# Arduino_Dimmer.net
KiCad netlist of a schematic drawn in EasyEDA
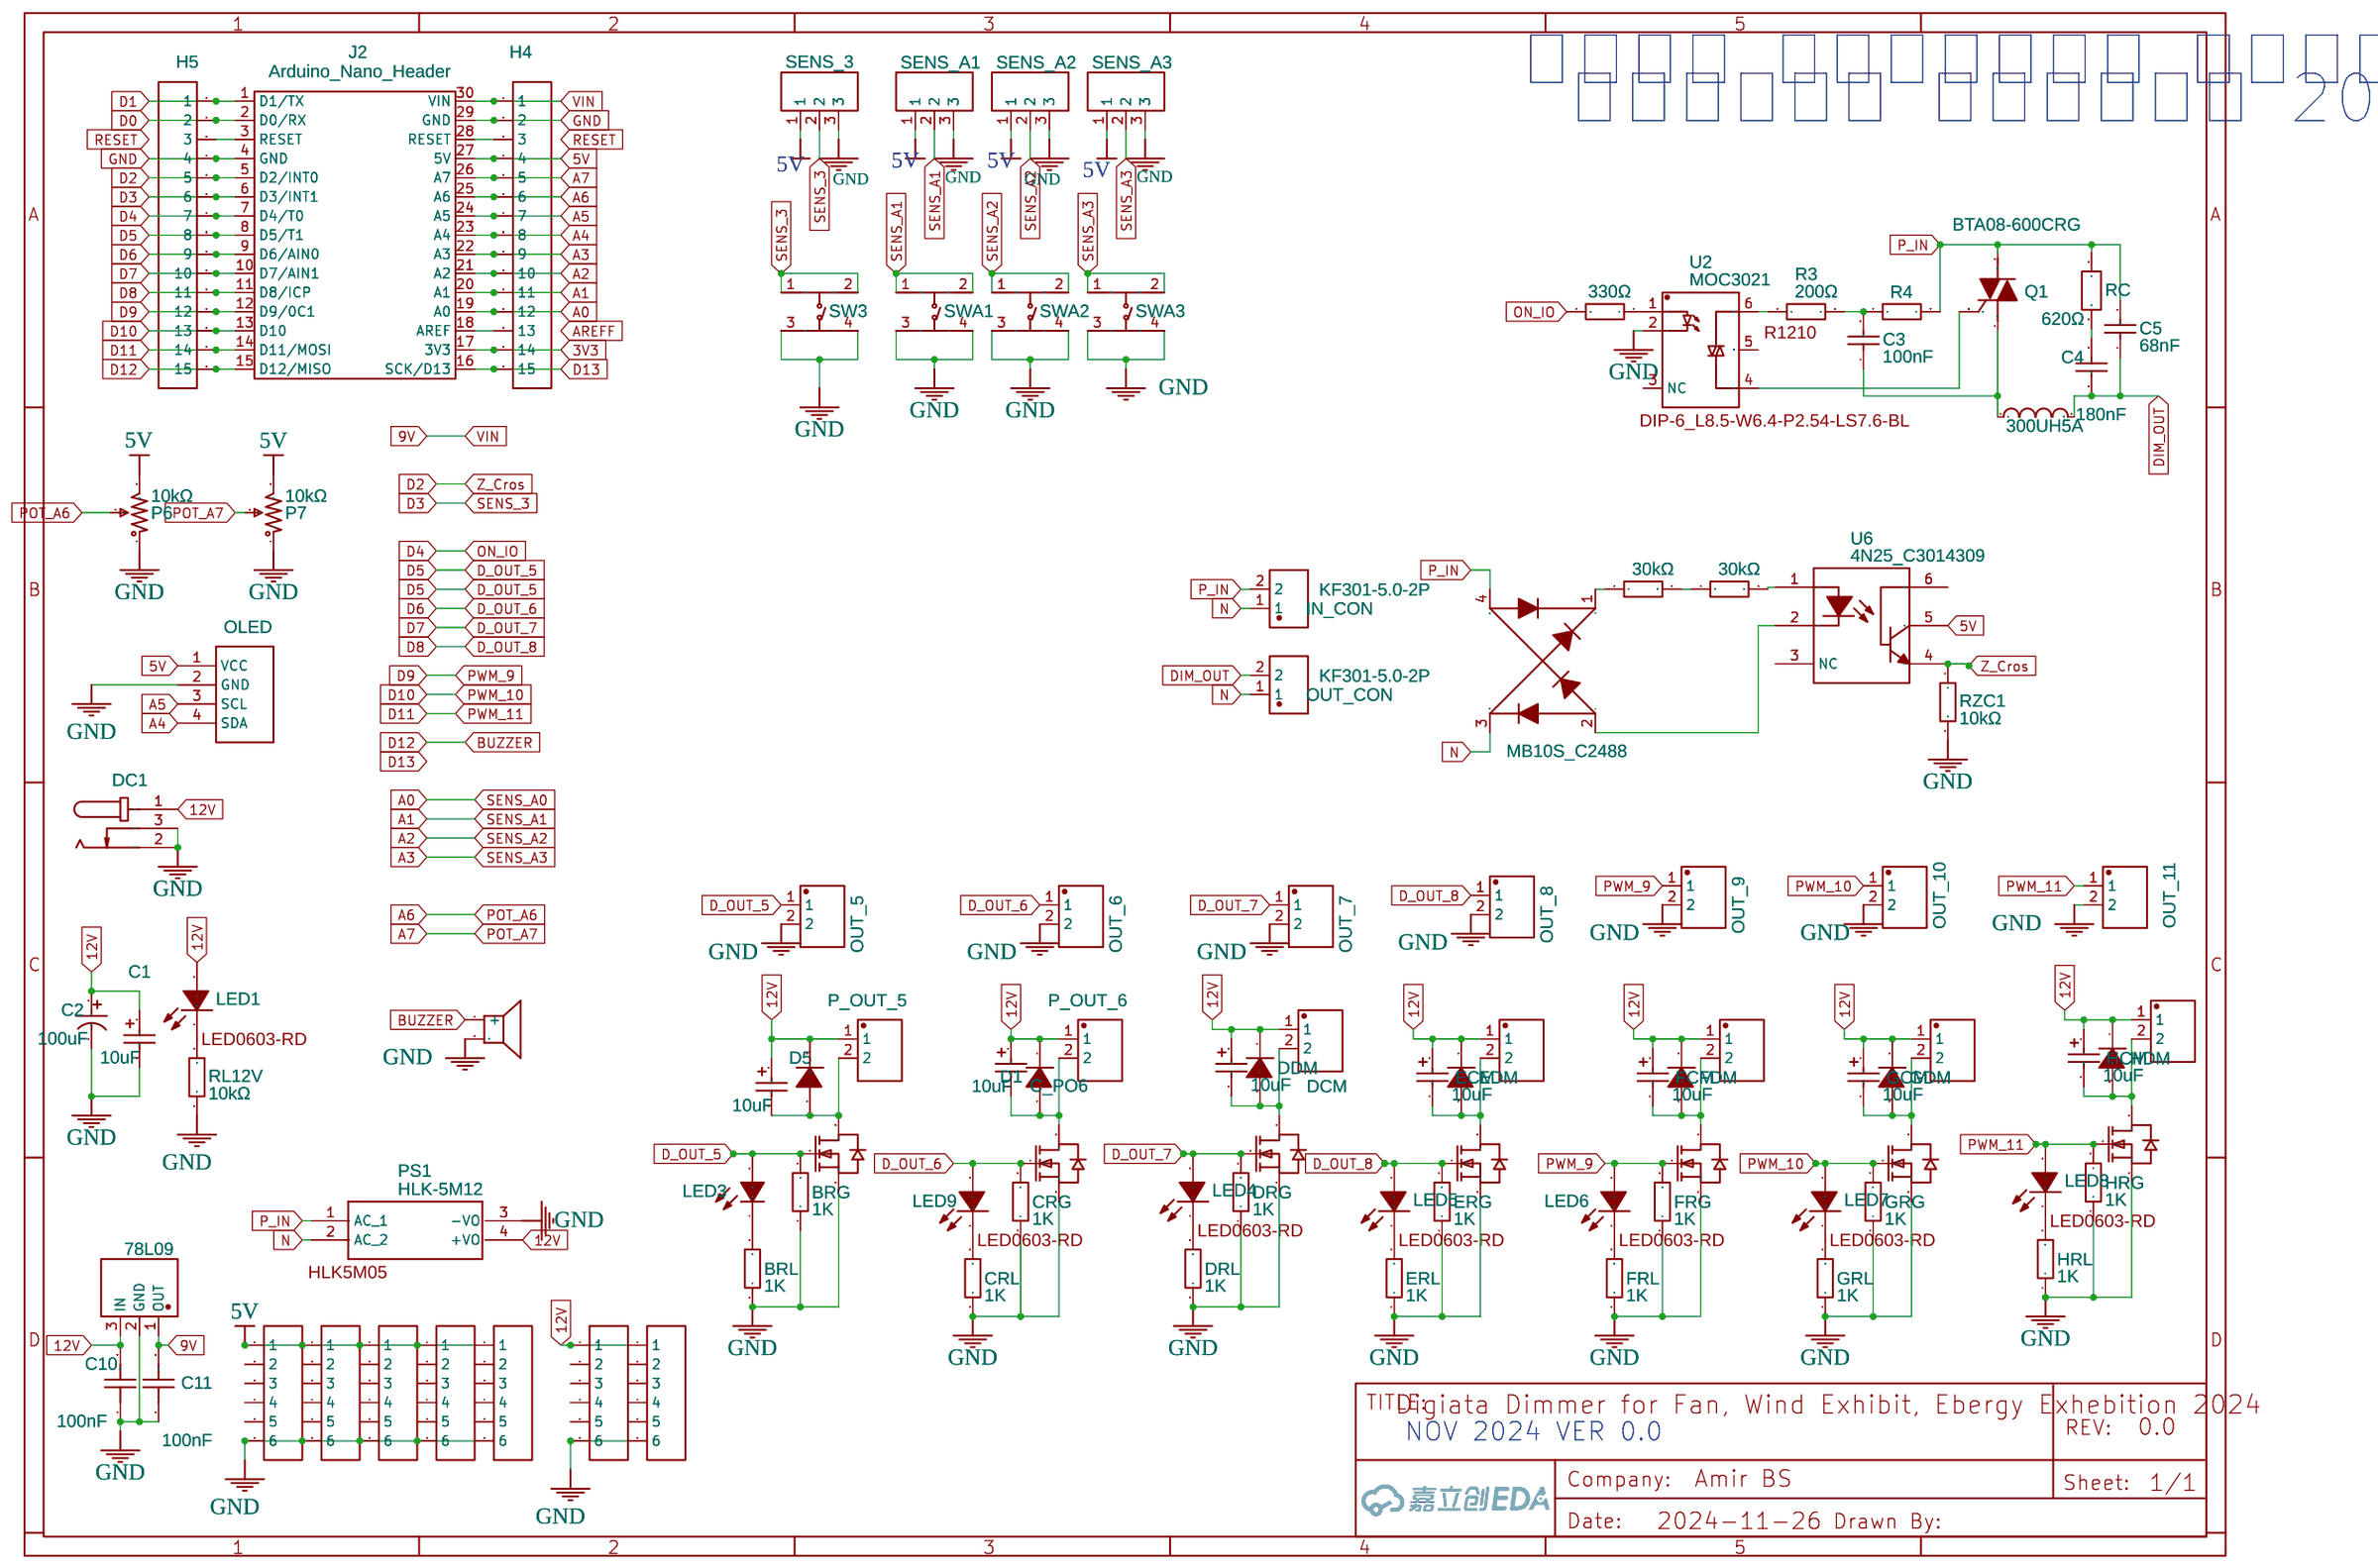
[diagram p0: schematic sheet]

(export (version "E")
  (design (tool "Eeschema 10.0.6"))
  (components
    (comp (ref "BQ")
      (value "Q")
      (fields (field (name "BOM_Manufacturer Part") "AO3400") (field (name "BOM_Supplier Part") "C5224189"))
      (libsource (lib "") (part "JSM2302_4"))
    )
    (comp (ref "BRG")
      (value "1K")
      (fields
        (field (name "BOM_Manufacturer Part") "0603WAF1001T5E")
        (field (name "BOM_Supplier Part") "C21190")
      )
      (libsource (lib "") (part "0603WAF1001T5E_4"))
    )
    (comp (ref "BRL")
      (value "1K")
      (fields
        (field (name "BOM_Manufacturer Part") "0603WAF1001T5E")
        (field (name "BOM_Supplier Part") "C21190")
      )
      (libsource (lib "") (part "0603WAF1001T5E_11"))
    )
    (comp (ref "BUZZER1")
      (value "BUZZER-12X9")
      (fields (field (name "Manufacturer Part") "buzzer-12X9"))
      (libsource (lib "") (part "BUZZER-12X9"))
    )
    (comp (ref "C1")
      (value "10uF")
      (fields (field (name "Manufacturer Part") "TAJA106K016RNJ") (field (name "Manufacturer") "Kyocera AVX"))
      (libsource (lib "") (part "TAJA106K016RNJ_6"))
    )
    (comp (ref "C2")
      (value "100uF")
      (fields
        (field (name "Manufacturer Part") "KM107M035E11RR0VH2FP0")
        (field (name "Manufacturer") "CX(承兴)")
      )
      (libsource (lib "") (part "100uF 35V 6.3*11"))
    )
    (comp (ref "C3")
      (value "100nF")
      (fields (field (name "Manufacturer Part") "MP2104K27C3R6LC") (field (name "Manufacturer") "SRD(圣融达)"))
      (libsource (lib "") (part "MP2104KGC3RLC"))
    )
    (comp (ref "C4")
      (value "180nF")
      (fields
        (field (name "Manufacturer Part") "MPP184J2G1306106LC")
        (field (name "Manufacturer") "SRD(圣融达)")
      )
      (libsource (lib "") (part "MPP184J4130610LC"))
    )
    (comp (ref "C5")
      (value "68nF")
      (fields
        (field (name "Manufacturer Part") "MPP683J2G1305095LC")
        (field (name "Manufacturer") "SRD(圣融达)")
      )
      (libsource (lib "") (part "MPP683J4130509LC"))
    )
    (comp (ref "C10")
      (value "100nF")
      (fields
        (field (name "Manufacturer Part") "CC0603KRX7R9BB104")
        (field (name "Manufacturer") "YAGEO(国巨)")
      )
      (libsource (lib "") (part "CC0603KRX7R9BB104"))
    )
    (comp (ref "C11")
      (value "100nF")
      (fields
        (field (name "Manufacturer Part") "CC0603KRX7R9BB104")
        (field (name "Manufacturer") "YAGEO(国巨)")
      )
      (libsource (lib "") (part "CC0603KRX7R9BB104"))
    )
    (comp (ref "CQ")
      (value "Q")
      (fields (field (name "BOM_Manufacturer Part") "AO3400") (field (name "BOM_Supplier Part") "C5224189"))
      (libsource (lib "") (part "JSM2302_2"))
    )
    (comp (ref "CRG")
      (value "1K")
      (fields
        (field (name "BOM_Manufacturer Part") "0603WAF1001T5E")
        (field (name "BOM_Supplier Part") "C21190")
      )
      (libsource (lib "") (part "0603WAF1001T5E_2"))
    )
    (comp (ref "CRL")
      (value "1K")
      (fields
        (field (name "BOM_Manufacturer Part") "0603WAF1001T5E")
        (field (name "BOM_Supplier Part") "C21190")
      )
      (libsource (lib "") (part "0603WAF1001T5E_1"))
    )
    (comp (ref "C_PO5")
      (value "10uF")
      (fields (field (name "Manufacturer Part") "TAJA106K016RNJ") (field (name "Manufacturer") "Kyocera AVX"))
      (libsource (lib "") (part "TAJA106K016RNJ"))
    )
    (comp (ref "C_PO6")
      (value "10uF")
      (fields (field (name "Manufacturer Part") "TAJA106K016RNJ") (field (name "Manufacturer") "Kyocera AVX"))
      (libsource (lib "") (part "TAJA106K016RNJ"))
    )
    (comp (ref "D1")
      (value "M7_C95872")
      (fields (field (name "Manufacturer Part") "M7") (field (name "Manufacturer") "MDD"))
      (libsource (lib "") (part "M7_C95872"))
    )
    (comp (ref "D2")
      (value "MB10S_C2488")
      (fields (field (name "Manufacturer Part") "MB10S") (field (name "Manufacturer") "MDD(辰达半导体)"))
      (libsource (lib "") (part "MB10S_C2488"))
    )
    (comp (ref "D5")
      (value "M7_C95872")
      (fields (field (name "Manufacturer Part") "M7") (field (name "Manufacturer") "MDD"))
      (libsource (lib "") (part "M7_C95872"))
    )
    (comp (ref "DC1")
      (value "DC")
      (fields
        (field (name "BOM_Manufacturer Part") "DC005-2.0MM")
        (field (name "BOM_Supplier Part") "C111567")
      )
      (libsource (lib "") (part "DC005-2.0MM"))
    )
    (comp (ref "DCM")
      (value "10uF")
      (fields (field (name "Manufacturer Part") "TAJA106K016RNJ") (field (name "Manufacturer") "Kyocera AVX"))
      (libsource (lib "") (part "TAJA106K016RNJ_4"))
    )
    (comp (ref "DCON")
      (value "KF2510-2A")
      (fields (field (name "BOM_Supplier Part") "C27543"))
      (libsource (lib "") (part "KF2510-2A_5"))
    )
    (comp (ref "DDM")
      (value "1N4007")
      (fields (field (name "BOM_Manufacturer Part") "1N4007F") (field (name "BOM_Supplier Part") "C110856"))
      (libsource (lib "") (part "1N4007F"))
    )
    (comp (ref "DQ")
      (value "Q")
      (fields (field (name "BOM_Manufacturer Part") "AO3400") (field (name "BOM_Supplier Part") "C5224189"))
      (libsource (lib "") (part "JSM2302"))
    )
    (comp (ref "DRG")
      (value "1K")
      (fields
        (field (name "BOM_Manufacturer Part") "0603WAF1001T5E")
        (field (name "BOM_Supplier Part") "C21190")
      )
      (libsource (lib "") (part "0603WAF1001T5E_13"))
    )
    (comp (ref "DRL")
      (value "1K")
      (fields
        (field (name "BOM_Manufacturer Part") "0603WAF1001T5E")
        (field (name "BOM_Supplier Part") "C21190")
      )
      (libsource (lib "") (part "0603WAF1001T5E_8"))
    )
    (comp (ref "ECM")
      (value "10uF")
      (fields (field (name "Manufacturer Part") "TAJA106K016RNJ") (field (name "Manufacturer") "Kyocera AVX"))
      (libsource (lib "") (part "TAJA106K016RNJ_1"))
    )
    (comp (ref "ECON")
      (value "KF2510-2A")
      (fields (field (name "BOM_Supplier Part") "C27543"))
      (libsource (lib "") (part "KF2510-2A_6"))
    )
    (comp (ref "EDM")
      (value "1N4007")
      (fields (field (name "BOM_Manufacturer Part") "1N4007F") (field (name "BOM_Supplier Part") "C110856"))
      (libsource (lib "") (part "1N4007F_4"))
    )
    (comp (ref "EQ")
      (value "Q")
      (fields (field (name "BOM_Manufacturer Part") "AO3400") (field (name "BOM_Supplier Part") "C5224189"))
      (libsource (lib "") (part "JSM2302_3"))
    )
    (comp (ref "ERG")
      (value "1K")
      (fields
        (field (name "BOM_Manufacturer Part") "0603WAF1001T5E")
        (field (name "BOM_Supplier Part") "C21190")
      )
      (libsource (lib "") (part "0603WAF1001T5E_3"))
    )
    (comp (ref "ERL")
      (value "1K")
      (fields
        (field (name "BOM_Manufacturer Part") "0603WAF1001T5E")
        (field (name "BOM_Supplier Part") "C21190")
      )
      (libsource (lib "") (part "0603WAF1001T5E_7"))
    )
    (comp (ref "FCM")
      (value "10uF")
      (fields (field (name "Manufacturer Part") "TAJA106K016RNJ") (field (name "Manufacturer") "Kyocera AVX"))
      (libsource (lib "") (part "TAJA106K016RNJ_5"))
    )
    (comp (ref "FCON")
      (value "KF2510-2A")
      (fields (field (name "BOM_Supplier Part") "C27543"))
      (libsource (lib "") (part "KF2510-2A_3"))
    )
    (comp (ref "FDM")
      (value "1N4007")
      (fields (field (name "BOM_Manufacturer Part") "1N4007F") (field (name "BOM_Supplier Part") "C110856"))
      (libsource (lib "") (part "1N4007F_1"))
    )
    (comp (ref "FQ")
      (value "Q")
      (fields (field (name "BOM_Manufacturer Part") "AO3400") (field (name "BOM_Supplier Part") "C5224189"))
      (libsource (lib "") (part "JSM2302_5"))
    )
    (comp (ref "FRG")
      (value "1K")
      (fields
        (field (name "BOM_Manufacturer Part") "0603WAF1001T5E")
        (field (name "BOM_Supplier Part") "C21190")
      )
      (libsource (lib "") (part "0603WAF1001T5E_12"))
    )
    (comp (ref "FRL")
      (value "1K")
      (fields
        (field (name "BOM_Manufacturer Part") "0603WAF1001T5E")
        (field (name "BOM_Supplier Part") "C21190")
      )
      (libsource (lib "") (part "0603WAF1001T5E_6"))
    )
    (comp (ref "GCM")
      (value "10uF")
      (fields (field (name "Manufacturer Part") "TAJA106K016RNJ") (field (name "Manufacturer") "Kyocera AVX"))
      (libsource (lib "") (part "TAJA106K016RNJ_2"))
    )
    (comp (ref "GCON")
      (value "KF2510-2A")
      (fields (field (name "BOM_Supplier Part") "C27543"))
      (libsource (lib "") (part "KF2510-2A_1"))
    )
    (comp (ref "GDM")
      (value "1N4007")
      (fields (field (name "BOM_Manufacturer Part") "1N4007F") (field (name "BOM_Supplier Part") "C110856"))
      (libsource (lib "") (part "1N4007F_2"))
    )
    (comp (ref "GQ")
      (value "Q")
      (fields (field (name "BOM_Manufacturer Part") "AO3400") (field (name "BOM_Supplier Part") "C5224189"))
      (libsource (lib "") (part "JSM2302_6"))
    )
    (comp (ref "GRG")
      (value "1K")
      (fields
        (field (name "BOM_Manufacturer Part") "0603WAF1001T5E")
        (field (name "BOM_Supplier Part") "C21190")
      )
      (libsource (lib "") (part "0603WAF1001T5E_10"))
    )
    (comp (ref "GRL")
      (value "1K")
      (fields
        (field (name "BOM_Manufacturer Part") "0603WAF1001T5E")
        (field (name "BOM_Supplier Part") "C21190")
      )
      (libsource (lib "") (part "0603WAF1001T5E_5"))
    )
    (comp (ref "H1")
      (value "HDR-F-2.54_1x6")
      (fields (field (name "BOM_Supplier Part") "C40877"))
      (libsource (lib "") (part "HDR-F-2.54_1x6"))
    )
    (comp (ref "H2")
      (value "HDR-F-2.54_1x6")
      (fields (field (name "BOM_Supplier Part") "C40877"))
      (libsource (lib "") (part "HDR-F-2.54_1x6"))
    )
    (comp (ref "H3")
      (value "HDR-F-2.54_1x6")
      (fields (field (name "BOM_Supplier Part") "C40877"))
      (libsource (lib "") (part "HDR-F-2.54_1x6"))
    )
    (comp (ref "H4")
      (value "HDR-F-2.54_1x15")
      (fields (field (name "BOM_Supplier Part") "C124408"))
      (libsource (lib "") (part "HDR-F-2.54_1x15_1"))
    )
    (comp (ref "H5")
      (value "HDR-F-2.54_1x15")
      (fields (field (name "BOM_Supplier Part") "C124408"))
      (libsource (lib "") (part "HDR-F-2.54_1x15"))
    )
    (comp (ref "H6")
      (value "HDR-F-2.54_1x6")
      (fields (field (name "BOM_Supplier Part") "C40877"))
      (libsource (lib "") (part "HDR-F-2.54_1x6"))
    )
    (comp (ref "H7")
      (value "HDR-F-2.54_1x6")
      (fields (field (name "BOM_Supplier Part") "C40877"))
      (libsource (lib "") (part "HDR-F-2.54_1x6"))
    )
    (comp (ref "H8")
      (value "HDR-F-2.54_1x6")
      (fields (field (name "BOM_Supplier Part") "C40877"))
      (libsource (lib "") (part "HDR-F-2.54_1x6"))
    )
    (comp (ref "H11")
      (value "HDR-F-2.54_1x6")
      (fields (field (name "BOM_Supplier Part") "C40877"))
      (libsource (lib "") (part "HDR-F-2.54_1x6"))
    )
    (comp (ref "HCM")
      (value "10uF")
      (fields (field (name "Manufacturer Part") "TAJA106K016RNJ") (field (name "Manufacturer") "Kyocera AVX"))
      (libsource (lib "") (part "TAJA106K016RNJ_3"))
    )
    (comp (ref "HCON")
      (value "KF2510-2A")
      (fields (field (name "BOM_Supplier Part") "C27543"))
      (libsource (lib "") (part "KF2510-2A_2"))
    )
    (comp (ref "HDM")
      (value "1N4007")
      (fields (field (name "BOM_Manufacturer Part") "1N4007F") (field (name "BOM_Supplier Part") "C110856"))
      (libsource (lib "") (part "1N4007F_3"))
    )
    (comp (ref "HQ")
      (value "Q")
      (fields (field (name "BOM_Manufacturer Part") "AO3400") (field (name "BOM_Supplier Part") "C5224189"))
      (libsource (lib "") (part "JSM2302_1"))
    )
    (comp (ref "HRG")
      (value "1K")
      (fields
        (field (name "BOM_Manufacturer Part") "0603WAF1001T5E")
        (field (name "BOM_Supplier Part") "C21190")
      )
      (libsource (lib "") (part "0603WAF1001T5E_9"))
    )
    (comp (ref "HRL")
      (value "1K")
      (fields
        (field (name "BOM_Manufacturer Part") "0603WAF1001T5E")
        (field (name "BOM_Supplier Part") "C21190")
      )
      (libsource (lib "") (part "0603WAF1001T5E"))
    )
    (comp (ref "IN_CON")
      (value "KF301-5.0-2P")
      (fields (field (name "Manufacturer") "KEFA(科发)"))
      (libsource (lib "") (part "KF301-5.0-2P"))
    )
    (comp (ref "J2") (value "Arduino_Nano_Header") (libsource (lib "") (part "Arduino_Nano_Header")))
    (comp (ref "LED1")
      (value "KT-0603R")
      (fields (field (name "Manufacturer") "KENTO"))
      (libsource (lib "") (part "KT-0603R"))
    )
    (comp (ref "LED3")
      (value "19-213/Y2C-CQ2R2L/3T(CY)")
      (fields (field (name "Manufacturer") "EVERLIGHT(亿光)"))
      (libsource (lib "") (part "19-213/Y2C-CQ2R2L/3T(CY)"))
    )
    (comp (ref "LED4")
      (value "KT-0603R")
      (fields (field (name "Manufacturer") "KENTO"))
      (libsource (lib "") (part "KT-0603R"))
    )
    (comp (ref "LED5")
      (value "KT-0603R")
      (fields (field (name "Manufacturer") "KENTO"))
      (libsource (lib "") (part "KT-0603R"))
    )
    (comp (ref "LED6")
      (value "KT-0603R")
      (fields (field (name "Manufacturer") "KENTO"))
      (libsource (lib "") (part "KT-0603R"))
    )
    (comp (ref "LED7")
      (value "KT-0603R")
      (fields (field (name "Manufacturer") "KENTO"))
      (libsource (lib "") (part "KT-0603R"))
    )
    (comp (ref "LED8")
      (value "KT-0603R")
      (fields (field (name "Manufacturer") "KENTO"))
      (libsource (lib "") (part "KT-0603R"))
    )
    (comp (ref "LED9")
      (value "KT-0603R")
      (fields (field (name "Manufacturer") "KENTO"))
      (libsource (lib "") (part "KT-0603R"))
    )
    (comp (ref "OLED")
      (value "1.3 inch OLED SSH1106 I2C 128x64 copy")
      (libsource (lib "") (part "1.3 inch OLED SSH1106 I2C 128x64 copy"))
    )
    (comp (ref "OUT_5")
      (value "KF2510-2A")
      (fields (field (name "BOM_Supplier Part") "C27543"))
      (libsource (lib "") (part "KF2510-2A"))
    )
    (comp (ref "OUT_6")
      (value "KF2510-2A")
      (fields (field (name "BOM_Supplier Part") "C27543"))
      (libsource (lib "") (part "KF2510-2A"))
    )
    (comp (ref "OUT_7")
      (value "KF2510-2A")
      (fields (field (name "BOM_Supplier Part") "C27543"))
      (libsource (lib "") (part "KF2510-2A"))
    )
    (comp (ref "OUT_8")
      (value "KF2510-2A")
      (fields (field (name "BOM_Supplier Part") "C27543"))
      (libsource (lib "") (part "KF2510-2A"))
    )
    (comp (ref "OUT_9")
      (value "KF2510-2A")
      (fields (field (name "BOM_Supplier Part") "C27543"))
      (libsource (lib "") (part "KF2510-2A"))
    )
    (comp (ref "OUT_10")
      (value "KF2510-2A")
      (fields (field (name "BOM_Supplier Part") "C27543"))
      (libsource (lib "") (part "KF2510-2A"))
    )
    (comp (ref "OUT_11")
      (value "KF2510-2A")
      (fields (field (name "BOM_Supplier Part") "C27543"))
      (libsource (lib "") (part "KF2510-2A"))
    )
    (comp (ref "OUT_CON")
      (value "KF301-5.0-2P")
      (fields (field (name "Manufacturer") "KEFA(科发)"))
      (libsource (lib "") (part "KF301-5.0-2P_1"))
    )
    (comp (ref "P6")
      (value "10kΩ")
      (fields (field (name "Manufacturer Part") "3296W-1-103") (field (name "Manufacturer") "BOCHEN(博晨)"))
      (libsource (lib "") (part "3296W-1-103"))
    )
    (comp (ref "P7")
      (value "10kΩ")
      (fields (field (name "Manufacturer Part") "3296W-1-103") (field (name "Manufacturer") "BOCHEN(博晨)"))
      (libsource (lib "") (part "3296W-1-103"))
    )
    (comp (ref "PS1") (value "HLK-5M12") (libsource (lib "") (part "HLK-5M05")))
    (comp (ref "P_OUT_5")
      (value "KF2510-2A")
      (fields (field (name "BOM_Supplier Part") "C27543"))
      (libsource (lib "") (part "KF2510-2A_4"))
    )
    (comp (ref "P_OUT_6")
      (value "KF2510-2A")
      (fields (field (name "BOM_Supplier Part") "C27543"))
      (libsource (lib "") (part "KF2510-2A_4"))
    )
    (comp (ref "Q1")
      (value "BTA08-600CRG")
      (fields (field (name "Manufacturer") "ST(意法半导体)"))
      (libsource (lib "") (part "BTA08-600CRG"))
    )
    (comp (ref "R1")
      (value "30kΩ")
      (fields
        (field (name "Manufacturer Part") "1812W2J0303T4E")
        (field (name "Manufacturer") "UNI-ROYAL(厚声)")
      )
      (libsource (lib "") (part "1812W2J0303T4E"))
    )
    (comp (ref "R2")
      (value "30kΩ")
      (fields
        (field (name "Manufacturer Part") "1812W2J0303T4E")
        (field (name "Manufacturer") "UNI-ROYAL(厚声)")
      )
      (libsource (lib "") (part "1812W2J0303T4E"))
    )
    (comp (ref "R3")
      (value "200Ω")
      (fields (field (name "Manufacturer Part") "RTT122000FTP") (field (name "Manufacturer") "RALEC(旺诠)"))
      (libsource (lib "") (part "RTT122000FTP"))
    )
    (comp (ref "R4")
      (value "680Ω")
      (fields (field (name "Manufacturer Part") "RMC12106805%N") (field (name "Manufacturer") "Tyohm(幸亚电阻)"))
      (libsource (lib "") (part "RMC12106805%N"))
    )
    (comp (ref "RC")
      (value "620Ω")
      (fields
        (field (name "Manufacturer Part") "25121WJ0621T4E")
        (field (name "Manufacturer") "UNI-ROYAL(厚声)")
      )
      (libsource (lib "") (part "25121WJ0621T4E"))
    )
    (comp (ref "RL12V")
      (value "10kΩ")
      (fields
        (field (name "BOM_Manufacturer Part") "0603WAF1002T5E")
        (field (name "BOM_Supplier Part") "C25804")
      )
      (libsource (lib "") (part "0603WAF1002T5E_1"))
    )
    (comp (ref "RONW")
      (value "330Ω")
      (fields
        (field (name "Manufacturer Part") "0603WAF3300T5E")
        (field (name "Manufacturer") "UNI-ROYAL(厚声)")
      )
      (libsource (lib "") (part "0603WAF3300T5E"))
    )
    (comp (ref "RZC1")
      (value "10kΩ")
      (fields
        (field (name "BOM_Manufacturer Part") "0603WAF1002T5E")
        (field (name "BOM_Supplier Part") "C25804")
      )
      (libsource (lib "") (part "0603WAF1002T5E"))
    )
    (comp (ref "SENS_3")
      (value "FK2510")
      (fields (field (name "Manufacturer Part") "2510-3A") (field (name "Manufacturer") "BOOMELE(博穆精密)"))
      (libsource (lib "") (part "kf2510_3A_1"))
    )
    (comp (ref "SENS_A1")
      (value "FK2510")
      (fields (field (name "Manufacturer Part") "2510-3A") (field (name "Manufacturer") "BOOMELE(博穆精密)"))
      (libsource (lib "") (part "kf2510_3A"))
    )
    (comp (ref "SENS_A2")
      (value "FK2510")
      (fields (field (name "Manufacturer Part") "2510-3A") (field (name "Manufacturer") "BOOMELE(博穆精密)"))
      (libsource (lib "") (part "kf2510_3A"))
    )
    (comp (ref "SENS_A3")
      (value "FK2510")
      (fields (field (name "Manufacturer Part") "2510-3A") (field (name "Manufacturer") "BOOMELE(博穆精密)"))
      (libsource (lib "") (part "kf2510_3A"))
    )
    (comp (ref "SW3")
      (value "TC-6610-7-160G")
      (fields (field (name "Manufacturer") "HCTL(华灿天禄)"))
      (libsource (lib "") (part "TC-6610-7-160G_1"))
    )
    (comp (ref "SWA1")
      (value "TC-6610-7-160G")
      (fields (field (name "Manufacturer") "HCTL(华灿天禄)"))
      (libsource (lib "") (part "TC-6610-7-160G"))
    )
    (comp (ref "SWA2")
      (value "TC-6610-7-160G")
      (fields (field (name "Manufacturer") "HCTL(华灿天禄)"))
      (libsource (lib "") (part "TC-6610-7-160G"))
    )
    (comp (ref "SWA3")
      (value "TC-6610-7-160G")
      (fields (field (name "Manufacturer") "HCTL(华灿天禄)"))
      (libsource (lib "") (part "TC-6610-7-160G"))
    )
    (comp (ref "U2")
      (value "MOC3021")
      (fields (field (name "Manufacturer") "LITEON(光宝)"))
      (libsource (lib "") (part "MOC3021"))
    )
    (comp (ref "U3") (value "300UH5A") (libsource (lib "") (part "300UH5A")))
    (comp (ref "U5")
      (value "78L09")
      (fields (field (name "Manufacturer Part") "78L09U 78L09") (field (name "Manufacturer") "CBI(创基)"))
      (libsource (lib "") (part "78L09U 78L09"))
    )
    (comp (ref "U6")
      (value "4N25_C3014309")
      (fields (field (name "Manufacturer Part") "4N25") (field (name "Manufacturer") "UMW(友台半导体)"))
      (libsource (lib "") (part "4N25_C3014309"))
    )
  )
  (nets
    (net (code "1") (name "3V3") (class "Default")
      (node (ref "H4") (pin "14") (pinfunction "14_14") (pintype "unspecified"))
      (node (ref "J2") (pin "17") (pinfunction "3V3_17") (pintype "unspecified"))
    )
    (net (code "2") (name "5V") (class "Default")
      (node (ref "H1") (pin "1") (pinfunction "1_1") (pintype "input"))
      (node (ref "H2") (pin "1") (pinfunction "1_1") (pintype "input"))
      (node (ref "H3") (pin "1") (pinfunction "1_1") (pintype "input"))
      (node (ref "H4") (pin "4") (pinfunction "4_4") (pintype "unspecified"))
      (node (ref "H7") (pin "1") (pinfunction "1_1") (pintype "input"))
      (node (ref "H8") (pin "1") (pinfunction "1_1") (pintype "input"))
      (node (ref "J2") (pin "27") (pinfunction "5V_27") (pintype "unspecified"))
      (node (ref "OLED") (pin "1") (pinfunction "VCC_1") (pintype "passive"))
      (node (ref "P6") (pin "3") (pinfunction "3_3") (pintype "unspecified"))
      (node (ref "P7") (pin "3") (pinfunction "3_3") (pintype "unspecified"))
      (node (ref "SENS_3") (pin "1") (pinfunction "1_1") (pintype "unspecified"))
      (node (ref "SENS_A1") (pin "1") (pinfunction "1_1") (pintype "unspecified"))
      (node (ref "SENS_A2") (pin "1") (pinfunction "1_1") (pintype "unspecified"))
      (node (ref "SENS_A3") (pin "1") (pinfunction "1_1") (pintype "unspecified"))
      (node (ref "U6") (pin "5") (pinfunction "5_5") (pintype "unspecified"))
    )
    (net (code "3") (name "9V") (class "Default")
      (node (ref "C11") (pin "2") (pinfunction "2_2") (pintype "unspecified"))
      (node (ref "H4") (pin "1") (pinfunction "1_1") (pintype "unspecified"))
      (node (ref "J2") (pin "30") (pinfunction "VIN_30") (pintype "unspecified"))
      (node (ref "U5") (pin "1") (pinfunction "OUT_1") (pintype "unspecified"))
    )
    (net (code "4") (name "12V") (class "Default")
      (node (ref "C1") (pin "1") (pinfunction "1_1") (pintype "input"))
      (node (ref "C10") (pin "2") (pinfunction "2_2") (pintype "unspecified"))
      (node (ref "C2") (pin "1") (pinfunction "1_1") (pintype "input"))
      (node (ref "C_PO5") (pin "1") (pinfunction "1_1") (pintype "input"))
      (node (ref "C_PO6") (pin "1") (pinfunction "1_1") (pintype "input"))
      (node (ref "D1") (pin "1") (pinfunction "K_1") (pintype "unspecified"))
      (node (ref "D5") (pin "1") (pinfunction "K_1") (pintype "unspecified"))
      (node (ref "DC1") (pin "1") (pinfunction "1_1") (pintype "unspecified"))
      (node (ref "DCM") (pin "1") (pinfunction "1_1") (pintype "input"))
      (node (ref "DCON") (pin "1") (pinfunction "1_1") (pintype "unspecified"))
      (node (ref "DDM") (pin "1") (pinfunction "C_1") (pintype "unspecified"))
      (node (ref "ECM") (pin "1") (pinfunction "1_1") (pintype "input"))
      (node (ref "ECON") (pin "1") (pinfunction "1_1") (pintype "unspecified"))
      (node (ref "EDM") (pin "1") (pinfunction "C_1") (pintype "unspecified"))
      (node (ref "FCM") (pin "1") (pinfunction "1_1") (pintype "input"))
      (node (ref "FCON") (pin "1") (pinfunction "1_1") (pintype "unspecified"))
      (node (ref "FDM") (pin "1") (pinfunction "C_1") (pintype "unspecified"))
      (node (ref "GCM") (pin "1") (pinfunction "1_1") (pintype "input"))
      (node (ref "GCON") (pin "1") (pinfunction "1_1") (pintype "unspecified"))
      (node (ref "GDM") (pin "1") (pinfunction "C_1") (pintype "unspecified"))
      (node (ref "H11") (pin "1") (pinfunction "1_1") (pintype "input"))
      (node (ref "H6") (pin "1") (pinfunction "1_1") (pintype "input"))
      (node (ref "HCM") (pin "1") (pinfunction "1_1") (pintype "input"))
      (node (ref "HCON") (pin "1") (pinfunction "1_1") (pintype "unspecified"))
      (node (ref "HDM") (pin "1") (pinfunction "C_1") (pintype "unspecified"))
      (node (ref "LED1") (pin "2") (pinfunction "A_2") (pintype "unspecified"))
      (node (ref "PS1") (pin "4") (pinfunction "+VO_4") (pintype "bidirectional"))
      (node (ref "P_OUT_5") (pin "1") (pinfunction "1_1") (pintype "unspecified"))
      (node (ref "P_OUT_6") (pin "1") (pinfunction "1_1") (pintype "unspecified"))
      (node (ref "U5") (pin "3") (pinfunction "IN_3") (pintype "unspecified"))
    )
    (net (code "5") (name "A0") (class "Default")
      (node (ref "H4") (pin "12") (pinfunction "12_12") (pintype "unspecified"))
      (node (ref "J2") (pin "19") (pinfunction "A0_19") (pintype "unspecified"))
    )
    (net (code "6") (name "A1") (class "Default")
      (node (ref "H4") (pin "11") (pinfunction "11_11") (pintype "unspecified"))
      (node (ref "J2") (pin "20") (pinfunction "A1_20") (pintype "unspecified"))
      (node (ref "SENS_A1") (pin "2") (pinfunction "2_2") (pintype "unspecified"))
      (node (ref "SWA1") (pin "1") (pinfunction "1_1") (pintype "unspecified"))
      (node (ref "SWA1") (pin "2") (pinfunction "2_2") (pintype "unspecified"))
    )
    (net (code "7") (name "A2") (class "Default")
      (node (ref "H4") (pin "10") (pinfunction "10_10") (pintype "unspecified"))
      (node (ref "J2") (pin "21") (pinfunction "A2_21") (pintype "unspecified"))
      (node (ref "SENS_A2") (pin "2") (pinfunction "2_2") (pintype "unspecified"))
      (node (ref "SWA2") (pin "1") (pinfunction "1_1") (pintype "unspecified"))
      (node (ref "SWA2") (pin "2") (pinfunction "2_2") (pintype "unspecified"))
    )
    (net (code "8") (name "A3") (class "Default")
      (node (ref "H4") (pin "9") (pinfunction "9_9") (pintype "unspecified"))
      (node (ref "J2") (pin "22") (pinfunction "A3_22") (pintype "unspecified"))
      (node (ref "SENS_A3") (pin "2") (pinfunction "2_2") (pintype "unspecified"))
      (node (ref "SWA3") (pin "1") (pinfunction "1_1") (pintype "unspecified"))
      (node (ref "SWA3") (pin "2") (pinfunction "2_2") (pintype "unspecified"))
    )
    (net (code "9") (name "A4") (class "Default")
      (node (ref "H4") (pin "8") (pinfunction "8_8") (pintype "unspecified"))
      (node (ref "J2") (pin "23") (pinfunction "A4_23") (pintype "unspecified"))
      (node (ref "OLED") (pin "4") (pinfunction "SDA_4") (pintype "bidirectional"))
    )
    (net (code "10") (name "A5") (class "Default")
      (node (ref "H4") (pin "7") (pinfunction "7_7") (pintype "unspecified"))
      (node (ref "J2") (pin "24") (pinfunction "A5_24") (pintype "unspecified"))
      (node (ref "OLED") (pin "3") (pinfunction "SCL_3") (pintype "bidirectional"))
    )
    (net (code "11") (name "A6") (class "Default")
      (node (ref "H4") (pin "6") (pinfunction "6_6") (pintype "unspecified"))
      (node (ref "J2") (pin "25") (pinfunction "A6_25") (pintype "unspecified"))
      (node (ref "P6") (pin "2") (pinfunction "2_2") (pintype "unspecified"))
    )
    (net (code "12") (name "A7") (class "Default")
      (node (ref "H4") (pin "5") (pinfunction "5_5") (pintype "unspecified"))
      (node (ref "J2") (pin "26") (pinfunction "A7_26") (pintype "unspecified"))
      (node (ref "P7") (pin "2") (pinfunction "2_2") (pintype "unspecified"))
    )
    (net (code "14") (name "BUZZER") (class "Default")
      (node (ref "BUZZER1") (pin "1") (pinfunction "+_1") (pintype "unspecified"))
      (node (ref "H5") (pin "15") (pinfunction "15_15") (pintype "unspecified"))
      (node (ref "J2") (pin "15") (pinfunction "D12/MISO_15") (pintype "unspecified"))
    )
    (net (code "15") (name "D0") (class "Default")
      (node (ref "H5") (pin "2") (pinfunction "2_2") (pintype "unspecified"))
      (node (ref "J2") (pin "2") (pinfunction "D0/RX_2") (pintype "unspecified"))
    )
    (net (code "16") (name "D1") (class "Default")
      (node (ref "H5") (pin "1") (pinfunction "1_1") (pintype "unspecified"))
      (node (ref "J2") (pin "1") (pinfunction "D1/TX_1") (pintype "unspecified"))
    )
    (net (code "17") (name "D2") (class "Default")
      (node (ref "H5") (pin "5") (pinfunction "5_5") (pintype "unspecified"))
      (node (ref "J2") (pin "5") (pinfunction "D2/INT0_5") (pintype "unspecified"))
      (node (ref "RZC1") (pin "1") (pinfunction "1_1") (pintype "input"))
      (node (ref "U6") (pin "4") (pinfunction "4_4") (pintype "unspecified"))
    )
    (net (code "18") (name "D3") (class "Default")
      (node (ref "H5") (pin "6") (pinfunction "6_6") (pintype "unspecified"))
      (node (ref "J2") (pin "6") (pinfunction "D3/INT1_6") (pintype "unspecified"))
      (node (ref "SENS_3") (pin "2") (pinfunction "2_2") (pintype "unspecified"))
      (node (ref "SW3") (pin "1") (pinfunction "1_1") (pintype "unspecified"))
      (node (ref "SW3") (pin "2") (pinfunction "2_2") (pintype "unspecified"))
    )
    (net (code "19") (name "D4") (class "Default")
      (node (ref "H5") (pin "7") (pinfunction "7_7") (pintype "unspecified"))
      (node (ref "J2") (pin "7") (pinfunction "D4/T0_7") (pintype "unspecified"))
      (node (ref "RONW") (pin "2") (pinfunction "2_2") (pintype "input"))
    )
    (net (code "20") (name "D5") (class "Default")
      (node (ref "BQ") (pin "1") (pinfunction "G_1") (pintype "unspecified"))
      (node (ref "BRG") (pin "2") (pinfunction "2_2") (pintype "input"))
      (node (ref "H5") (pin "8") (pinfunction "8_8") (pintype "unspecified"))
      (node (ref "J2") (pin "8") (pinfunction "D5/T1_8") (pintype "unspecified"))
      (node (ref "LED3") (pin "2") (pinfunction "A_2") (pintype "input"))
      (node (ref "OUT_5") (pin "1") (pinfunction "1_1") (pintype "unspecified"))
    )
    (net (code "21") (name "D6") (class "Default")
      (node (ref "CQ") (pin "1") (pinfunction "G_1") (pintype "unspecified"))
      (node (ref "CRG") (pin "2") (pinfunction "2_2") (pintype "input"))
      (node (ref "H5") (pin "9") (pinfunction "9_9") (pintype "unspecified"))
      (node (ref "J2") (pin "9") (pinfunction "D6/AIN0_9") (pintype "unspecified"))
      (node (ref "LED9") (pin "2") (pinfunction "A_2") (pintype "unspecified"))
      (node (ref "OUT_6") (pin "1") (pinfunction "1_1") (pintype "unspecified"))
    )
    (net (code "22") (name "D7") (class "Default")
      (node (ref "DQ") (pin "1") (pinfunction "G_1") (pintype "unspecified"))
      (node (ref "DRG") (pin "2") (pinfunction "2_2") (pintype "input"))
      (node (ref "H5") (pin "10") (pinfunction "10_10") (pintype "unspecified"))
      (node (ref "J2") (pin "10") (pinfunction "D7/AIN1_10") (pintype "unspecified"))
      (node (ref "LED4") (pin "2") (pinfunction "A_2") (pintype "unspecified"))
      (node (ref "OUT_7") (pin "1") (pinfunction "1_1") (pintype "unspecified"))
    )
    (net (code "23") (name "D8") (class "Default")
      (node (ref "EQ") (pin "1") (pinfunction "G_1") (pintype "unspecified"))
      (node (ref "ERG") (pin "2") (pinfunction "2_2") (pintype "input"))
      (node (ref "H5") (pin "11") (pinfunction "11_11") (pintype "unspecified"))
      (node (ref "J2") (pin "11") (pinfunction "D8/ICP_11") (pintype "unspecified"))
      (node (ref "LED5") (pin "2") (pinfunction "A_2") (pintype "unspecified"))
      (node (ref "OUT_8") (pin "1") (pinfunction "1_1") (pintype "unspecified"))
    )
    (net (code "24") (name "D9") (class "Default")
      (node (ref "FQ") (pin "1") (pinfunction "G_1") (pintype "unspecified"))
      (node (ref "FRG") (pin "2") (pinfunction "2_2") (pintype "input"))
      (node (ref "H5") (pin "12") (pinfunction "12_12") (pintype "unspecified"))
      (node (ref "J2") (pin "12") (pinfunction "D9/0C1_12") (pintype "unspecified"))
      (node (ref "LED6") (pin "2") (pinfunction "A_2") (pintype "unspecified"))
      (node (ref "OUT_9") (pin "1") (pinfunction "1_1") (pintype "unspecified"))
    )
    (net (code "25") (name "D10") (class "Default")
      (node (ref "GQ") (pin "1") (pinfunction "G_1") (pintype "unspecified"))
      (node (ref "GRG") (pin "2") (pinfunction "2_2") (pintype "input"))
      (node (ref "H5") (pin "13") (pinfunction "13_13") (pintype "unspecified"))
      (node (ref "J2") (pin "13") (pinfunction "D10_13") (pintype "unspecified"))
      (node (ref "LED7") (pin "2") (pinfunction "A_2") (pintype "unspecified"))
      (node (ref "OUT_10") (pin "1") (pinfunction "1_1") (pintype "unspecified"))
    )
    (net (code "26") (name "D11") (class "Default")
      (node (ref "H5") (pin "14") (pinfunction "14_14") (pintype "unspecified"))
      (node (ref "HQ") (pin "1") (pinfunction "G_1") (pintype "unspecified"))
      (node (ref "HRG") (pin "2") (pinfunction "2_2") (pintype "input"))
      (node (ref "J2") (pin "14") (pinfunction "D11/MOSI_14") (pintype "unspecified"))
      (node (ref "LED8") (pin "2") (pinfunction "A_2") (pintype "unspecified"))
      (node (ref "OUT_11") (pin "1") (pinfunction "1_1") (pintype "unspecified"))
    )
    (net (code "27") (name "D13") (class "Default")
      (node (ref "H4") (pin "15") (pinfunction "15_15") (pintype "unspecified"))
      (node (ref "J2") (pin "16") (pinfunction "SCK/D13_16") (pintype "unspecified"))
    )
    (net (code "28") (name "DIM_OUT") (class "Default")
      (node (ref "C4") (pin "1") (pinfunction "1_1") (pintype "input"))
      (node (ref "C5") (pin "1") (pinfunction "1_1") (pintype "input"))
      (node (ref "OUT_CON") (pin "2") (pinfunction "2_2") (pintype "unspecified"))
      (node (ref "U3") (pin "2") (pinfunction "2_2") (pintype "unspecified"))
    )
    (net (code "29") (name "GND") (class "Default")
      (node (ref "BQ") (pin "2") (pinfunction "S_2") (pintype "unspecified"))
      (node (ref "BRG") (pin "1") (pinfunction "1_1") (pintype "input"))
      (node (ref "BRL") (pin "1") (pinfunction "1_1") (pintype "input"))
      (node (ref "BUZZER1") (pin "2") (pinfunction "2_2") (pintype "unspecified"))
      (node (ref "C1") (pin "2") (pinfunction "2_2") (pintype "input"))
      (node (ref "C10") (pin "1") (pinfunction "1_1") (pintype "unspecified"))
      (node (ref "C11") (pin "1") (pinfunction "1_1") (pintype "unspecified"))
      (node (ref "C2") (pin "2") (pinfunction "2_2") (pintype "input"))
      (node (ref "CQ") (pin "2") (pinfunction "S_2") (pintype "unspecified"))
      (node (ref "CRG") (pin "1") (pinfunction "1_1") (pintype "input"))
      (node (ref "CRL") (pin "1") (pinfunction "1_1") (pintype "input"))
      (node (ref "DC1") (pin "2") (pinfunction "2_2") (pintype "unspecified"))
      (node (ref "DC1") (pin "3") (pinfunction "3_3") (pintype "unspecified"))
      (node (ref "DQ") (pin "2") (pinfunction "S_2") (pintype "unspecified"))
      (node (ref "DRG") (pin "1") (pinfunction "1_1") (pintype "input"))
      (node (ref "DRL") (pin "1") (pinfunction "1_1") (pintype "input"))
      (node (ref "EQ") (pin "2") (pinfunction "S_2") (pintype "unspecified"))
      (node (ref "ERG") (pin "1") (pinfunction "1_1") (pintype "input"))
      (node (ref "ERL") (pin "1") (pinfunction "1_1") (pintype "input"))
      (node (ref "FQ") (pin "2") (pinfunction "S_2") (pintype "unspecified"))
      (node (ref "FRG") (pin "1") (pinfunction "1_1") (pintype "input"))
      (node (ref "FRL") (pin "1") (pinfunction "1_1") (pintype "input"))
      (node (ref "GQ") (pin "2") (pinfunction "S_2") (pintype "unspecified"))
      (node (ref "GRG") (pin "1") (pinfunction "1_1") (pintype "input"))
      (node (ref "GRL") (pin "1") (pinfunction "1_1") (pintype "input"))
      (node (ref "H1") (pin "6") (pinfunction "6_6") (pintype "input"))
      (node (ref "H11") (pin "6") (pinfunction "6_6") (pintype "input"))
      (node (ref "H2") (pin "6") (pinfunction "6_6") (pintype "input"))
      (node (ref "H3") (pin "6") (pinfunction "6_6") (pintype "input"))
      (node (ref "H4") (pin "2") (pinfunction "2_2") (pintype "unspecified"))
      (node (ref "H5") (pin "4") (pinfunction "4_4") (pintype "unspecified"))
      (node (ref "H6") (pin "6") (pinfunction "6_6") (pintype "input"))
      (node (ref "H7") (pin "6") (pinfunction "6_6") (pintype "input"))
      (node (ref "H8") (pin "6") (pinfunction "6_6") (pintype "input"))
      (node (ref "HQ") (pin "2") (pinfunction "S_2") (pintype "unspecified"))
      (node (ref "HRG") (pin "1") (pinfunction "1_1") (pintype "input"))
      (node (ref "HRL") (pin "1") (pinfunction "1_1") (pintype "input"))
      (node (ref "J2") (pin "29") (pinfunction "GND_29") (pintype "unspecified"))
      (node (ref "J2") (pin "4") (pinfunction "GND_4") (pintype "unspecified"))
      (node (ref "OLED") (pin "2") (pinfunction "GND_2") (pintype "passive"))
      (node (ref "OUT_10") (pin "2") (pinfunction "2_2") (pintype "unspecified"))
      (node (ref "OUT_11") (pin "2") (pinfunction "2_2") (pintype "unspecified"))
      (node (ref "OUT_5") (pin "2") (pinfunction "2_2") (pintype "unspecified"))
      (node (ref "OUT_6") (pin "2") (pinfunction "2_2") (pintype "unspecified"))
      (node (ref "OUT_7") (pin "2") (pinfunction "2_2") (pintype "unspecified"))
      (node (ref "OUT_8") (pin "2") (pinfunction "2_2") (pintype "unspecified"))
      (node (ref "OUT_9") (pin "2") (pinfunction "2_2") (pintype "unspecified"))
      (node (ref "P6") (pin "1") (pinfunction "1_1") (pintype "unspecified"))
      (node (ref "P7") (pin "1") (pinfunction "1_1") (pintype "unspecified"))
      (node (ref "PS1") (pin "3") (pinfunction "-VO_3") (pintype "bidirectional"))
      (node (ref "RL12V") (pin "2") (pinfunction "2_2") (pintype "input"))
      (node (ref "RZC1") (pin "2") (pinfunction "2_2") (pintype "input"))
      (node (ref "SENS_3") (pin "3") (pinfunction "3_3") (pintype "unspecified"))
      (node (ref "SENS_A1") (pin "3") (pinfunction "3_3") (pintype "unspecified"))
      (node (ref "SENS_A2") (pin "3") (pinfunction "3_3") (pintype "unspecified"))
      (node (ref "SENS_A3") (pin "3") (pinfunction "3_3") (pintype "unspecified"))
      (node (ref "SW3") (pin "3") (pinfunction "3_3") (pintype "unspecified"))
      (node (ref "SW3") (pin "4") (pinfunction "4_4") (pintype "unspecified"))
      (node (ref "SWA1") (pin "3") (pinfunction "3_3") (pintype "unspecified"))
      (node (ref "SWA1") (pin "4") (pinfunction "4_4") (pintype "unspecified"))
      (node (ref "SWA2") (pin "3") (pinfunction "3_3") (pintype "unspecified"))
      (node (ref "SWA2") (pin "4") (pinfunction "4_4") (pintype "unspecified"))
      (node (ref "SWA3") (pin "3") (pinfunction "3_3") (pintype "unspecified"))
      (node (ref "SWA3") (pin "4") (pinfunction "4_4") (pintype "unspecified"))
      (node (ref "U2") (pin "2") (pinfunction "2_2") (pintype "unspecified"))
      (node (ref "U5") (pin "2") (pinfunction "GND_2") (pintype "unspecified"))
    )
    (net (code "30") (name "N") (class "Default")
      (node (ref "D2") (pin "3") (pinfunction "C2_3") (pintype "unspecified"))
      (node (ref "IN_CON") (pin "1") (pinfunction "1_1") (pintype "unspecified"))
      (node (ref "OUT_CON") (pin "1") (pinfunction "1_1") (pintype "unspecified"))
      (node (ref "PS1") (pin "2") (pinfunction "AC_2_2") (pintype "bidirectional"))
    )
    (net (code "31") (name "Net-(BQ-D)") (class "Default")
      (node (ref "BQ") (pin "3") (pinfunction "D_3") (pintype "unspecified"))
      (node (ref "C_PO5") (pin "2") (pinfunction "2_2") (pintype "input"))
      (node (ref "D5") (pin "2") (pinfunction "A_2") (pintype "unspecified"))
      (node (ref "P_OUT_5") (pin "2") (pinfunction "2_2") (pintype "unspecified"))
    )
    (net (code "32") (name "Net-(C3-Pad2)") (class "Default")
      (node (ref "C3") (pin "2") (pinfunction "2_2") (pintype "input"))
      (node (ref "R3") (pin "2") (pinfunction "2_2") (pintype "input"))
      (node (ref "R4") (pin "1") (pinfunction "1_1") (pintype "unspecified"))
    )
    (net (code "33") (name "Net-(C4-Pad2)") (class "Default")
      (node (ref "C4") (pin "2") (pinfunction "2_2") (pintype "input"))
      (node (ref "RC") (pin "1") (pinfunction "1_1") (pintype "unspecified"))
    )
    (net (code "34") (name "Net-(CQ-D)") (class "Default")
      (node (ref "CQ") (pin "3") (pinfunction "D_3") (pintype "unspecified"))
      (node (ref "C_PO6") (pin "2") (pinfunction "2_2") (pintype "input"))
      (node (ref "D1") (pin "2") (pinfunction "A_2") (pintype "unspecified"))
      (node (ref "P_OUT_6") (pin "2") (pinfunction "2_2") (pintype "unspecified"))
    )
    (net (code "35") (name "Net-(D2-+)") (class "Default")
      (node (ref "D2") (pin "1") (pinfunction "+_1") (pintype "unspecified"))
      (node (ref "R1") (pin "1") (pinfunction "1_1") (pintype "unspecified"))
    )
    (net (code "36") (name "Net-(D2--)") (class "Default")
      (node (ref "D2") (pin "2") (pinfunction "-_2") (pintype "unspecified"))
      (node (ref "U6") (pin "2") (pinfunction "2_2") (pintype "unspecified"))
    )
    (net (code "37") (name "Net-(DDM-A)") (class "Default")
      (node (ref "DCM") (pin "2") (pinfunction "2_2") (pintype "input"))
      (node (ref "DCON") (pin "2") (pinfunction "2_2") (pintype "unspecified"))
      (node (ref "DDM") (pin "2") (pinfunction "A_2") (pintype "unspecified"))
      (node (ref "DQ") (pin "3") (pinfunction "D_3") (pintype "unspecified"))
    )
    (net (code "38") (name "Net-(EDM-A)") (class "Default")
      (node (ref "ECM") (pin "2") (pinfunction "2_2") (pintype "input"))
      (node (ref "ECON") (pin "2") (pinfunction "2_2") (pintype "unspecified"))
      (node (ref "EDM") (pin "2") (pinfunction "A_2") (pintype "unspecified"))
      (node (ref "EQ") (pin "3") (pinfunction "D_3") (pintype "unspecified"))
    )
    (net (code "39") (name "Net-(FDM-A)") (class "Default")
      (node (ref "FCM") (pin "2") (pinfunction "2_2") (pintype "input"))
      (node (ref "FCON") (pin "2") (pinfunction "2_2") (pintype "unspecified"))
      (node (ref "FDM") (pin "2") (pinfunction "A_2") (pintype "unspecified"))
      (node (ref "FQ") (pin "3") (pinfunction "D_3") (pintype "unspecified"))
    )
    (net (code "40") (name "Net-(GDM-A)") (class "Default")
      (node (ref "GCM") (pin "2") (pinfunction "2_2") (pintype "input"))
      (node (ref "GCON") (pin "2") (pinfunction "2_2") (pintype "unspecified"))
      (node (ref "GDM") (pin "2") (pinfunction "A_2") (pintype "unspecified"))
      (node (ref "GQ") (pin "3") (pinfunction "D_3") (pintype "unspecified"))
    )
    (net (code "41") (name "Net-(H4-Pad3)") (class "Default")
      (node (ref "H4") (pin "3") (pinfunction "3_3") (pintype "unspecified"))
      (node (ref "J2") (pin "28") (pinfunction "RESET_28") (pintype "unspecified"))
    )
    (net (code "42") (name "Net-(H5-Pad3)") (class "Default")
      (node (ref "H5") (pin "3") (pinfunction "3_3") (pintype "unspecified"))
      (node (ref "J2") (pin "3") (pinfunction "RESET_3") (pintype "unspecified"))
    )
    (net (code "43") (name "Net-(HDM-A)") (class "Default")
      (node (ref "HCM") (pin "2") (pinfunction "2_2") (pintype "input"))
      (node (ref "HCON") (pin "2") (pinfunction "2_2") (pintype "unspecified"))
      (node (ref "HDM") (pin "2") (pinfunction "A_2") (pintype "unspecified"))
      (node (ref "HQ") (pin "3") (pinfunction "D_3") (pintype "unspecified"))
    )
    (net (code "44") (name "Net-(J2-AREF)") (class "Default")
      (node (ref "H4") (pin "13") (pinfunction "13_13") (pintype "unspecified"))
      (node (ref "J2") (pin "18") (pinfunction "AREF_18") (pintype "unspecified"))
    )
    (net (code "45") (name "Net-(LED1-K)") (class "Default")
      (node (ref "LED1") (pin "1") (pinfunction "K_1") (pintype "unspecified"))
      (node (ref "RL12V") (pin "1") (pinfunction "1_1") (pintype "input"))
    )
    (net (code "46") (name "Net-(LED3-C)") (class "Default")
      (node (ref "BRL") (pin "2") (pinfunction "2_2") (pintype "input"))
      (node (ref "LED3") (pin "1") (pinfunction "C_1") (pintype "input"))
    )
    (net (code "47") (name "Net-(LED4-K)") (class "Default")
      (node (ref "DRL") (pin "2") (pinfunction "2_2") (pintype "input"))
      (node (ref "LED4") (pin "1") (pinfunction "K_1") (pintype "unspecified"))
    )
    (net (code "48") (name "Net-(LED5-K)") (class "Default")
      (node (ref "ERL") (pin "2") (pinfunction "2_2") (pintype "input"))
      (node (ref "LED5") (pin "1") (pinfunction "K_1") (pintype "unspecified"))
    )
    (net (code "49") (name "Net-(LED6-K)") (class "Default")
      (node (ref "FRL") (pin "2") (pinfunction "2_2") (pintype "input"))
      (node (ref "LED6") (pin "1") (pinfunction "K_1") (pintype "unspecified"))
    )
    (net (code "50") (name "Net-(LED7-K)") (class "Default")
      (node (ref "GRL") (pin "2") (pinfunction "2_2") (pintype "input"))
      (node (ref "LED7") (pin "1") (pinfunction "K_1") (pintype "unspecified"))
    )
    (net (code "51") (name "Net-(LED8-K)") (class "Default")
      (node (ref "HRL") (pin "2") (pinfunction "2_2") (pintype "input"))
      (node (ref "LED8") (pin "1") (pinfunction "K_1") (pintype "unspecified"))
    )
    (net (code "52") (name "Net-(LED9-K)") (class "Default")
      (node (ref "CRL") (pin "2") (pinfunction "2_2") (pintype "input"))
      (node (ref "LED9") (pin "1") (pinfunction "K_1") (pintype "unspecified"))
    )
    (net (code "53") (name "Net-(Q1-G)") (class "Default")
      (node (ref "Q1") (pin "3") (pinfunction "G_3") (pintype "unspecified"))
      (node (ref "U2") (pin "4") (pinfunction "E_4") (pintype "unspecified"))
    )
    (net (code "54") (name "Net-(Q1-M1)") (class "Default")
      (node (ref "C3") (pin "1") (pinfunction "1_1") (pintype "input"))
      (node (ref "Q1") (pin "1") (pinfunction "M1_1") (pintype "unspecified"))
      (node (ref "U3") (pin "1") (pinfunction "1_1") (pintype "unspecified"))
    )
    (net (code "55") (name "Net-(R1-Pad2)") (class "Default")
      (node (ref "R1") (pin "2") (pinfunction "2_2") (pintype "unspecified"))
      (node (ref "R2") (pin "1") (pinfunction "1_1") (pintype "unspecified"))
    )
    (net (code "56") (name "Net-(R2-Pad2)") (class "Default")
      (node (ref "R2") (pin "2") (pinfunction "2_2") (pintype "unspecified"))
      (node (ref "U6") (pin "1") (pinfunction "1_1") (pintype "unspecified"))
    )
    (net (code "57") (name "Net-(RONW-Pad1)") (class "Default")
      (node (ref "RONW") (pin "1") (pinfunction "1_1") (pintype "input"))
      (node (ref "U2") (pin "1") (pinfunction "1_1") (pintype "unspecified"))
    )
    (net (code "58") (name "Net-(U2-BASE)") (class "Default")
      (node (ref "R3") (pin "1") (pinfunction "1_1") (pintype "input"))
      (node (ref "U2") (pin "6") (pinfunction "BASE_6") (pintype "unspecified"))
    )
    (net (code "59") (name "P_IN") (class "Default")
      (node (ref "C5") (pin "2") (pinfunction "2_2") (pintype "input"))
      (node (ref "D2") (pin "4") (pinfunction "C1_4") (pintype "unspecified"))
      (node (ref "IN_CON") (pin "2") (pinfunction "2_2") (pintype "unspecified"))
      (node (ref "PS1") (pin "1") (pinfunction "AC_1_1") (pintype "bidirectional"))
      (node (ref "Q1") (pin "2") (pinfunction "M2_2") (pintype "unspecified"))
      (node (ref "R4") (pin "2") (pinfunction "2_2") (pintype "unspecified"))
      (node (ref "RC") (pin "2") (pinfunction "2_2") (pintype "unspecified"))
    )
    (net (code "61") (name "unconnected-(H1-Pad2)") (class "Default")
      (node (ref "H1") (pin "2") (pinfunction "2_2") (pintype "input"))
    )
    (net (code "62") (name "unconnected-(H1-Pad3)") (class "Default")
      (node (ref "H1") (pin "3") (pinfunction "3_3") (pintype "input"))
    )
    (net (code "63") (name "unconnected-(H1-Pad4)") (class "Default")
      (node (ref "H1") (pin "4") (pinfunction "4_4") (pintype "input"))
    )
    (net (code "64") (name "unconnected-(H1-Pad5)") (class "Default")
      (node (ref "H1") (pin "5") (pinfunction "5_5") (pintype "input"))
    )
    (net (code "65") (name "unconnected-(H2-Pad2)") (class "Default")
      (node (ref "H2") (pin "2") (pinfunction "2_2") (pintype "input"))
    )
    (net (code "66") (name "unconnected-(H2-Pad3)") (class "Default")
      (node (ref "H2") (pin "3") (pinfunction "3_3") (pintype "input"))
    )
    (net (code "67") (name "unconnected-(H2-Pad4)") (class "Default")
      (node (ref "H2") (pin "4") (pinfunction "4_4") (pintype "input"))
    )
    (net (code "68") (name "unconnected-(H2-Pad5)") (class "Default")
      (node (ref "H2") (pin "5") (pinfunction "5_5") (pintype "input"))
    )
    (net (code "69") (name "unconnected-(H3-Pad2)") (class "Default")
      (node (ref "H3") (pin "2") (pinfunction "2_2") (pintype "input"))
    )
    (net (code "70") (name "unconnected-(H3-Pad3)") (class "Default")
      (node (ref "H3") (pin "3") (pinfunction "3_3") (pintype "input"))
    )
    (net (code "71") (name "unconnected-(H3-Pad4)") (class "Default")
      (node (ref "H3") (pin "4") (pinfunction "4_4") (pintype "input"))
    )
    (net (code "72") (name "unconnected-(H3-Pad5)") (class "Default")
      (node (ref "H3") (pin "5") (pinfunction "5_5") (pintype "input"))
    )
    (net (code "73") (name "unconnected-(H6-Pad2)") (class "Default")
      (node (ref "H6") (pin "2") (pinfunction "2_2") (pintype "input"))
    )
    (net (code "74") (name "unconnected-(H6-Pad3)") (class "Default")
      (node (ref "H6") (pin "3") (pinfunction "3_3") (pintype "input"))
    )
    (net (code "75") (name "unconnected-(H6-Pad4)") (class "Default")
      (node (ref "H6") (pin "4") (pinfunction "4_4") (pintype "input"))
    )
    (net (code "76") (name "unconnected-(H6-Pad5)") (class "Default")
      (node (ref "H6") (pin "5") (pinfunction "5_5") (pintype "input"))
    )
    (net (code "77") (name "unconnected-(H7-Pad2)") (class "Default")
      (node (ref "H7") (pin "2") (pinfunction "2_2") (pintype "input"))
    )
    (net (code "78") (name "unconnected-(H7-Pad3)") (class "Default")
      (node (ref "H7") (pin "3") (pinfunction "3_3") (pintype "input"))
    )
    (net (code "79") (name "unconnected-(H7-Pad4)") (class "Default")
      (node (ref "H7") (pin "4") (pinfunction "4_4") (pintype "input"))
    )
    (net (code "80") (name "unconnected-(H7-Pad5)") (class "Default")
      (node (ref "H7") (pin "5") (pinfunction "5_5") (pintype "input"))
    )
    (net (code "81") (name "unconnected-(H8-Pad2)") (class "Default")
      (node (ref "H8") (pin "2") (pinfunction "2_2") (pintype "input"))
    )
    (net (code "82") (name "unconnected-(H8-Pad3)") (class "Default")
      (node (ref "H8") (pin "3") (pinfunction "3_3") (pintype "input"))
    )
    (net (code "83") (name "unconnected-(H8-Pad4)") (class "Default")
      (node (ref "H8") (pin "4") (pinfunction "4_4") (pintype "input"))
    )
    (net (code "84") (name "unconnected-(H8-Pad5)") (class "Default")
      (node (ref "H8") (pin "5") (pinfunction "5_5") (pintype "input"))
    )
    (net (code "85") (name "unconnected-(H11-Pad2)") (class "Default")
      (node (ref "H11") (pin "2") (pinfunction "2_2") (pintype "input"))
    )
    (net (code "86") (name "unconnected-(H11-Pad3)") (class "Default")
      (node (ref "H11") (pin "3") (pinfunction "3_3") (pintype "input"))
    )
    (net (code "87") (name "unconnected-(H11-Pad4)") (class "Default")
      (node (ref "H11") (pin "4") (pinfunction "4_4") (pintype "input"))
    )
    (net (code "88") (name "unconnected-(H11-Pad5)") (class "Default")
      (node (ref "H11") (pin "5") (pinfunction "5_5") (pintype "input"))
    )
    (net (code "89") (name "unconnected-(U2-NC-Pad3)") (class "Default")
      (node (ref "U2") (pin "3") (pinfunction "NC_3") (pintype "unspecified"))
    )
    (net (code "90") (name "unconnected-(U2-SUB-Pad5)") (class "Default")
      (node (ref "U2") (pin "5") (pinfunction "SUB_5") (pintype "unspecified"))
    )
    (net (code "91") (name "unconnected-(U6-NC-Pad3)") (class "Default")
      (node (ref "U6") (pin "3") (pinfunction "NC_3") (pintype "unspecified"))
    )
    (net (code "92") (name "unconnected-(U6-Pad6)") (class "Default")
      (node (ref "U6") (pin "6") (pinfunction "6_6") (pintype "unspecified"))
    )
  )
)
